# SchematicJSON.net
KiCad netlist of a schematic drawn in EasyEDA
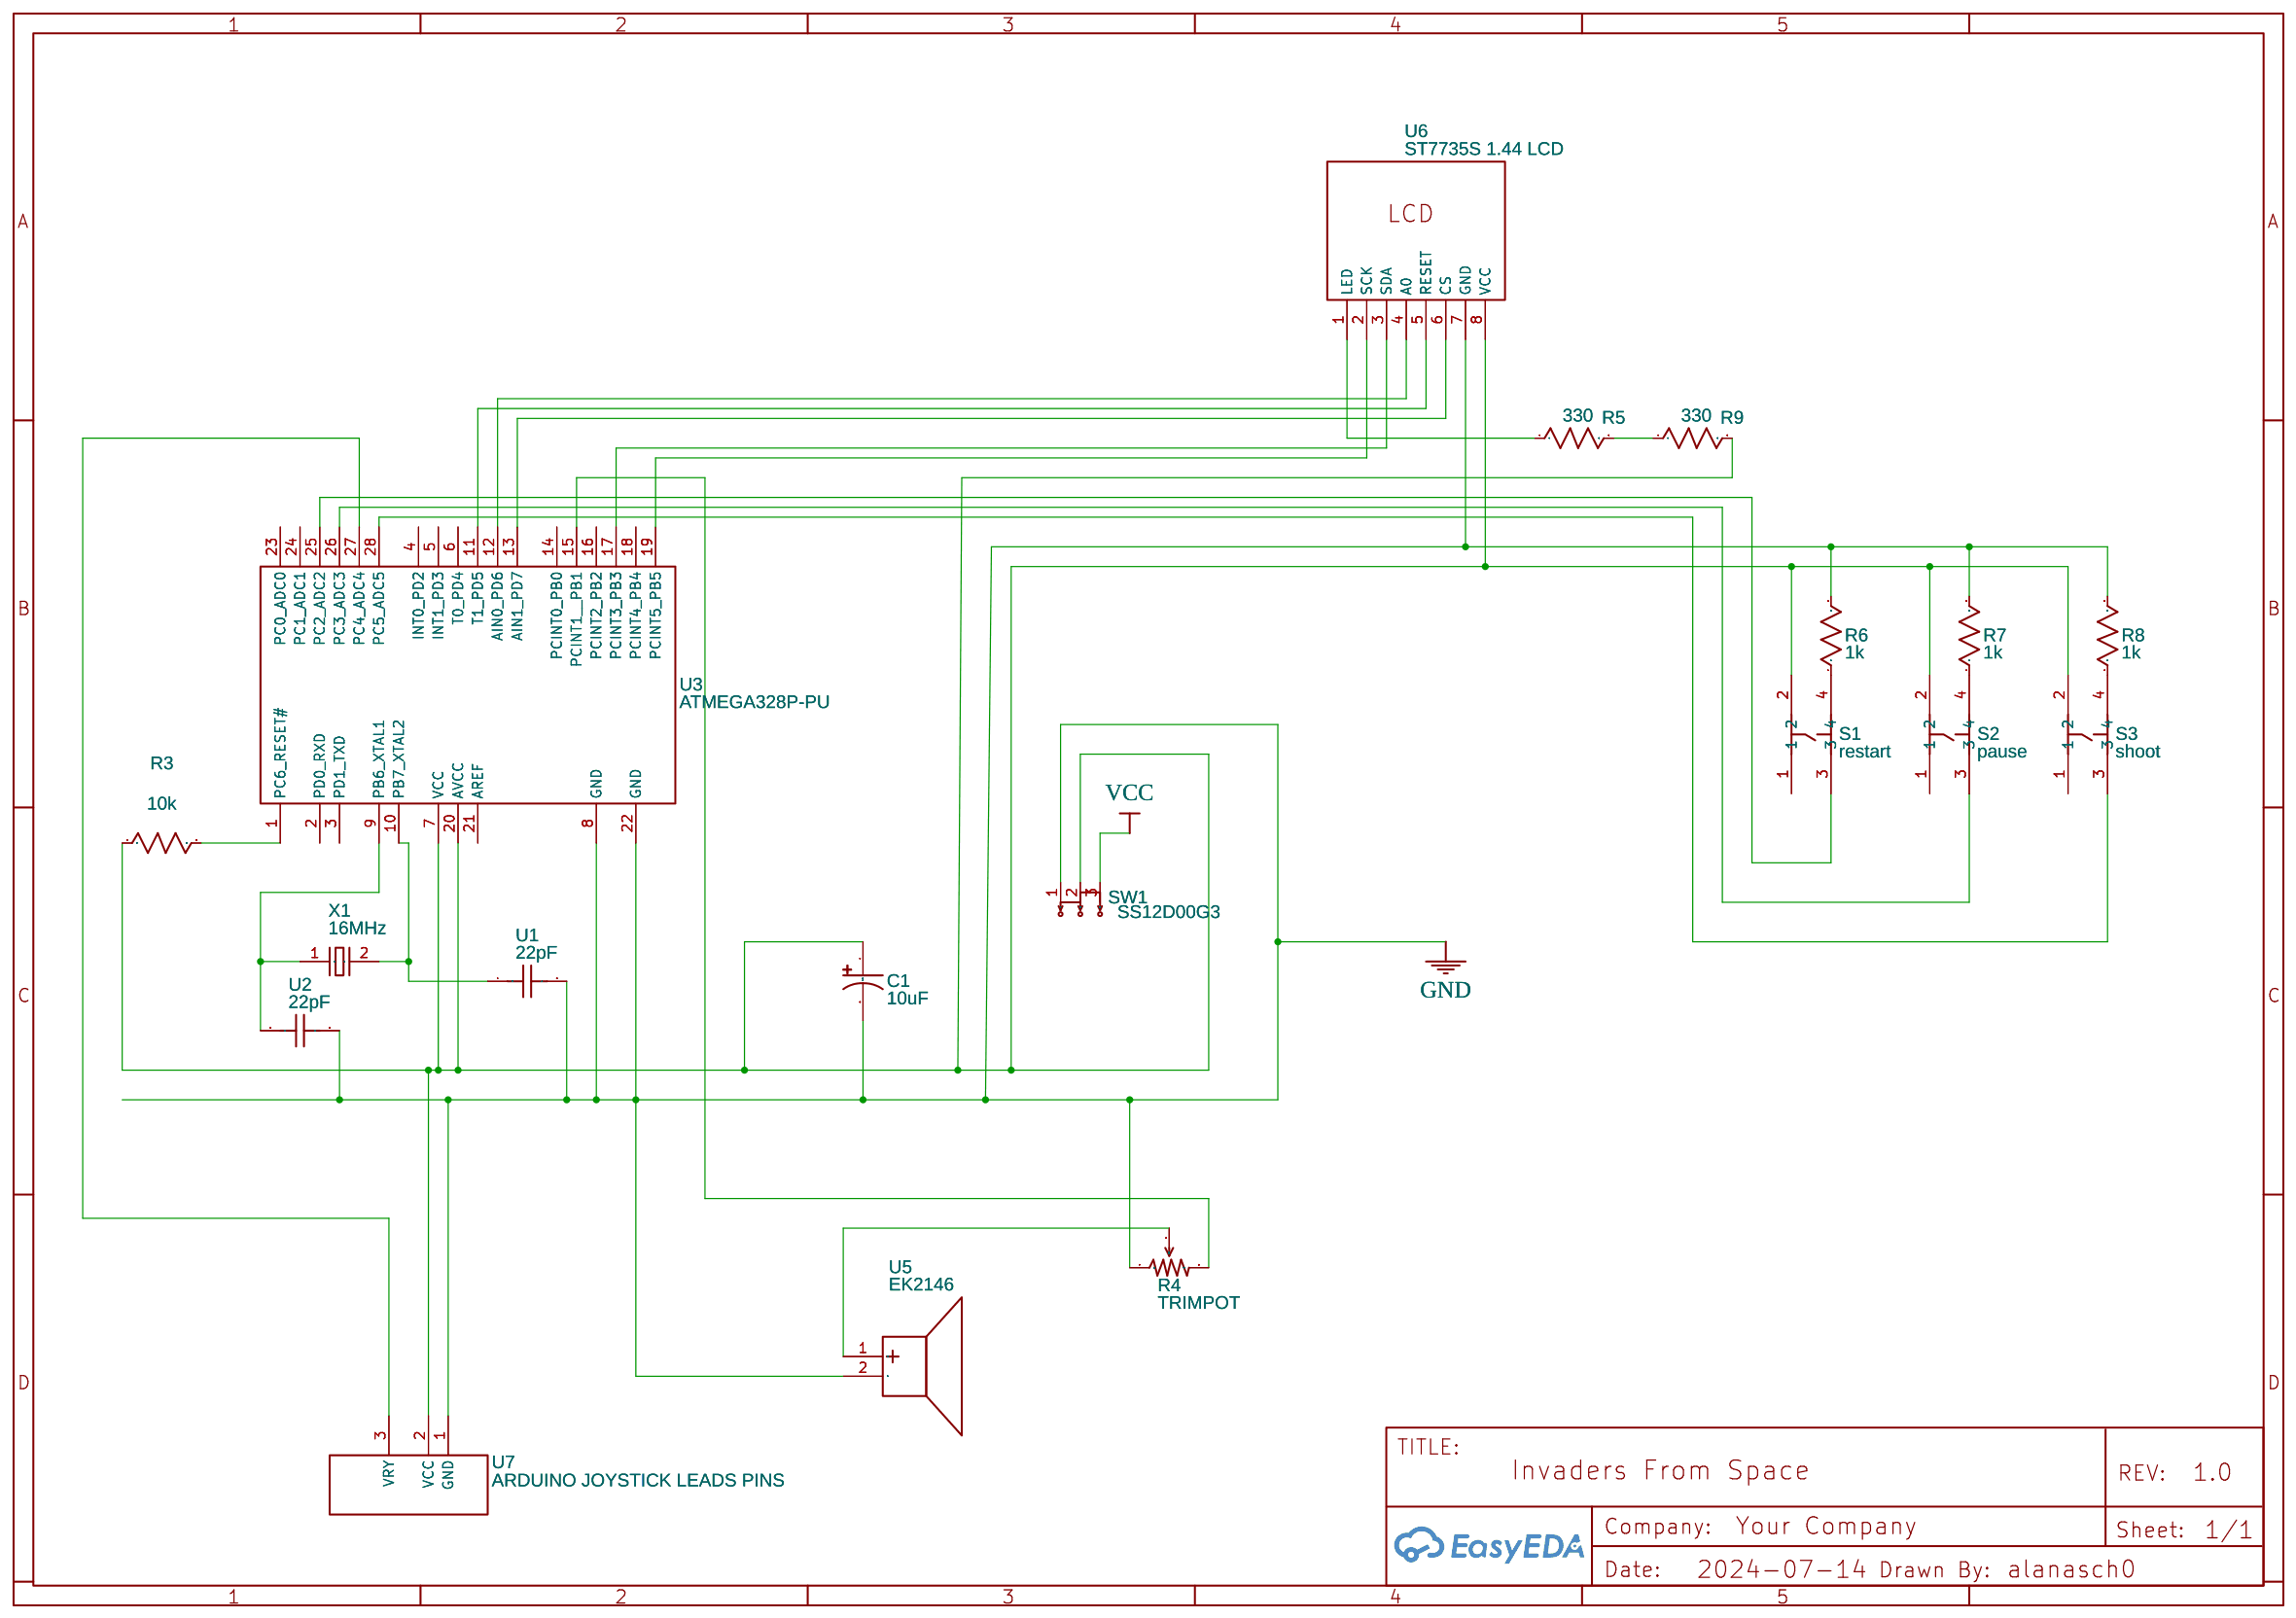
[diagram p0: schematic sheet]

(export (version "E")
  (design (tool "Eeschema 10.0.6"))
  (components
    (comp (ref "C1")
      (value "10uF")
      (fields
        (field (name "Manufacturer Part") "NFA 400V10 M 10*20")
        (field (name "Manufacturer") "SAMYOUNG(韩国三莹)")
      )
      (libsource (lib "") (part "NFA-400VB10-M-10*20"))
    )
    (comp (ref "R3") (value "10k") (libsource (lib "") (part "R_0603_US")))
    (comp (ref "R4") (value "TRIMPOT") (libsource (lib "") (part "TRIMPOT")))
    (comp (ref "R5") (value "330") (libsource (lib "") (part "R_0603_US")))
    (comp (ref "R6") (value "1k") (libsource (lib "") (part "R_0603_US_1")))
    (comp (ref "R7") (value "1k") (libsource (lib "") (part "R_0603_US_1")))
    (comp (ref "R8") (value "1k") (libsource (lib "") (part "R_0603_US_1")))
    (comp (ref "R9") (value "330") (libsource (lib "") (part "R_0603_US")))
    (comp (ref "S1")
      (value "restart")
      (fields (field (name "Manufacturer Part") "3101") (field (name "Manufacturer") "Adafruit"))
      (libsource (lib "") (part "Soft Tactile Button 8x8 (Adafruit 3101)"))
    )
    (comp (ref "S2")
      (value "pause")
      (fields (field (name "Manufacturer Part") "3101") (field (name "Manufacturer") "Adafruit"))
      (libsource (lib "") (part "Soft Tactile Button 8x8 (Adafruit 3101)"))
    )
    (comp (ref "S3")
      (value "shoot")
      (fields (field (name "Manufacturer Part") "3101") (field (name "Manufacturer") "Adafruit"))
      (libsource (lib "") (part "Soft Tactile Button 8x8 (Adafruit 3101)"))
    )
    (comp (ref "SW1") (value "SS12D00G3") (libsource (lib "") (part "SS12D00G3")))
    (comp (ref "U1")
      (value "22pF")
      (fields (field (name "Manufacturer Part") "K220J15C0GF53L2") (field (name "Manufacturer") "VISHAY(威世)"))
      (libsource (lib "") (part "K220J15C0GF53L2"))
    )
    (comp (ref "U2")
      (value "22pF")
      (fields (field (name "Manufacturer Part") "K220J15C0GF53L2") (field (name "Manufacturer") "VISHAY(威世)"))
      (libsource (lib "") (part "K220J15C0GF53L2"))
    )
    (comp (ref "U3")
      (value "ATMEGA328P-PU")
      (fields (field (name "Manufacturer") "MICROCHIP(美国微芯)"))
      (libsource (lib "") (part "ATMEGA328P-PU"))
    )
    (comp (ref "U5")
      (value "EK2146")
      (fields (field (name "Manufacturer") "Gikfun"))
      (libsource (lib "") (part "EK2146"))
    )
    (comp (ref "U6") (value "ST7735S 1.44 LCD") (libsource (lib "") (part "ST7735S 1.44 LCD")))
    (comp (ref "U7")
      (value "ARDUINO JOYSTICK LEADS PINS")
      (libsource (lib "") (part "ARDUINO JOYSTICK LEADS PINS"))
    )
    (comp (ref "X1")
      (value "16MHz")
      (fields
        (field (name "Manufacturer Part") "AS-16.000-18")
        (field (name "Manufacturer") "RALTRON(美国纬创电子)")
      )
      (libsource (lib "") (part "AS-16.000-18"))
    )
  )
  (nets
    (net (code "1") (name "GND") (class "Default")
      (node (ref "C1") (pin "2") (pinfunction "2_2") (pintype "unspecified"))
      (node (ref "R4") (pin "1") (pinfunction "CCW_1") (pintype "unspecified"))
      (node (ref "R6") (pin "2") (pinfunction "2_2") (pintype "unspecified"))
      (node (ref "R7") (pin "2") (pinfunction "2_2") (pintype "unspecified"))
      (node (ref "R8") (pin "2") (pinfunction "2_2") (pintype "unspecified"))
      (node (ref "SW1") (pin "1") (pinfunction "1_1") (pintype "unspecified"))
      (node (ref "U1") (pin "2") (pinfunction "2_2") (pintype "unspecified"))
      (node (ref "U2") (pin "2") (pinfunction "2_2") (pintype "unspecified"))
      (node (ref "U3") (pin "22") (pinfunction "GND_22") (pintype "passive"))
      (node (ref "U3") (pin "8") (pinfunction "GND_8") (pintype "passive"))
      (node (ref "U5") (pin "2") (pinfunction "2_2") (pintype "unspecified"))
      (node (ref "U6") (pin "7") (pinfunction "GND_7") (pintype "unspecified"))
      (node (ref "U7") (pin "1") (pinfunction "GND_1") (pintype "unspecified"))
    )
    (net (code "2") (name "Net-(R4-CW)") (class "Default")
      (node (ref "R4") (pin "3") (pinfunction "CW_3") (pintype "unspecified"))
      (node (ref "U3") (pin "15") (pinfunction "PCINT1__PB1_15") (pintype "bidirectional"))
    )
    (net (code "3") (name "Net-(R4-WIPER)") (class "Default")
      (node (ref "R4") (pin "2") (pinfunction "WIPER_2") (pintype "unspecified"))
      (node (ref "U5") (pin "1") (pinfunction "1_1") (pintype "unspecified"))
    )
    (net (code "4") (name "Net-(R5-Pad2)") (class "Default")
      (node (ref "R5") (pin "2") (pinfunction "2_2") (pintype "unspecified"))
      (node (ref "R9") (pin "1") (pinfunction "1_1") (pintype "unspecified"))
    )
    (net (code "5") (name "Net-(R6-Pad1)") (class "Default")
      (node (ref "R6") (pin "1") (pinfunction "1_1") (pintype "unspecified"))
      (node (ref "S1") (pin "4") (pinfunction "4_4") (pintype "unspecified"))
    )
    (net (code "6") (name "Net-(R7-Pad1)") (class "Default")
      (node (ref "R7") (pin "1") (pinfunction "1_1") (pintype "unspecified"))
      (node (ref "S2") (pin "4") (pinfunction "4_4") (pintype "unspecified"))
    )
    (net (code "7") (name "Net-(R8-Pad1)") (class "Default")
      (node (ref "R8") (pin "1") (pinfunction "1_1") (pintype "unspecified"))
      (node (ref "S3") (pin "4") (pinfunction "4_4") (pintype "unspecified"))
    )
    (net (code "8") (name "Net-(U3-AIN0_PD6)") (class "Default")
      (node (ref "U3") (pin "12") (pinfunction "AIN0_PD6_12") (pintype "bidirectional"))
      (node (ref "U6") (pin "4") (pinfunction "A0_4") (pintype "unspecified"))
    )
    (net (code "9") (name "Net-(U3-AIN1_PD7)") (class "Default")
      (node (ref "U3") (pin "13") (pinfunction "AIN1_PD7_13") (pintype "bidirectional"))
      (node (ref "U6") (pin "6") (pinfunction "CS_6") (pintype "unspecified"))
    )
    (net (code "10") (name "Net-(U3-AVCC)") (class "Default")
      (node (ref "C1") (pin "1") (pinfunction "1_1") (pintype "unspecified"))
      (node (ref "R3") (pin "1") (pinfunction "1_1") (pintype "unspecified"))
      (node (ref "R9") (pin "2") (pinfunction "2_2") (pintype "unspecified"))
      (node (ref "S1") (pin "2") (pinfunction "2_2") (pintype "unspecified"))
      (node (ref "S2") (pin "2") (pinfunction "2_2") (pintype "unspecified"))
      (node (ref "S3") (pin "2") (pinfunction "2_2") (pintype "unspecified"))
      (node (ref "SW1") (pin "2") (pinfunction "2_2") (pintype "unspecified"))
      (node (ref "U3") (pin "20") (pinfunction "AVCC_20") (pintype "passive"))
      (node (ref "U3") (pin "7") (pinfunction "VCC_7") (pintype "passive"))
      (node (ref "U6") (pin "8") (pinfunction "VCC_8") (pintype "unspecified"))
      (node (ref "U7") (pin "2") (pinfunction "VCC_2") (pintype "unspecified"))
    )
    (net (code "11") (name "Net-(U3-PB6_XTAL1)") (class "Default")
      (node (ref "U2") (pin "1") (pinfunction "1_1") (pintype "unspecified"))
      (node (ref "U3") (pin "9") (pinfunction "PB6_XTAL1_9") (pintype "bidirectional"))
      (node (ref "X1") (pin "1") (pinfunction "1_1") (pintype "input"))
    )
    (net (code "12") (name "Net-(U3-PB7_XTAL2)") (class "Default")
      (node (ref "U1") (pin "1") (pinfunction "1_1") (pintype "unspecified"))
      (node (ref "U3") (pin "10") (pinfunction "PB7_XTAL2_10") (pintype "bidirectional"))
      (node (ref "X1") (pin "2") (pinfunction "2_2") (pintype "input"))
    )
    (net (code "13") (name "Net-(U3-PC2_ADC2)") (class "Default")
      (node (ref "S1") (pin "3") (pinfunction "3_3") (pintype "unspecified"))
      (node (ref "U3") (pin "25") (pinfunction "PC2_ADC2_25") (pintype "bidirectional"))
    )
    (net (code "14") (name "Net-(U3-PC3_ADC3)") (class "Default")
      (node (ref "S2") (pin "3") (pinfunction "3_3") (pintype "unspecified"))
      (node (ref "U3") (pin "26") (pinfunction "PC3_ADC3_26") (pintype "bidirectional"))
    )
    (net (code "15") (name "Net-(U3-PC4_ADC4)") (class "Default")
      (node (ref "U3") (pin "27") (pinfunction "PC4_ADC4_27") (pintype "bidirectional"))
      (node (ref "U7") (pin "3") (pinfunction "VRY_3") (pintype "unspecified"))
    )
    (net (code "16") (name "Net-(U3-PC5_ADC5)") (class "Default")
      (node (ref "S3") (pin "3") (pinfunction "3_3") (pintype "unspecified"))
      (node (ref "U3") (pin "28") (pinfunction "PC5_ADC5_28") (pintype "bidirectional"))
    )
    (net (code "17") (name "Net-(U3-PC6_RESET#)") (class "Default")
      (node (ref "R3") (pin "2") (pinfunction "2_2") (pintype "unspecified"))
      (node (ref "U3") (pin "1") (pinfunction "PC6_RESET#_1") (pintype "bidirectional"))
    )
    (net (code "18") (name "Net-(U3-PCINT3_PB3)") (class "Default")
      (node (ref "U3") (pin "17") (pinfunction "PCINT3_PB3_17") (pintype "bidirectional"))
      (node (ref "U6") (pin "3") (pinfunction "SDA_3") (pintype "unspecified"))
    )
    (net (code "19") (name "Net-(U3-PCINT5_PB5)") (class "Default")
      (node (ref "U3") (pin "19") (pinfunction "PCINT5_PB5_19") (pintype "bidirectional"))
      (node (ref "U6") (pin "2") (pinfunction "SCK_2") (pintype "unspecified"))
    )
    (net (code "20") (name "Net-(U3-T1_PD5)") (class "Default")
      (node (ref "U3") (pin "11") (pinfunction "T1_PD5_11") (pintype "bidirectional"))
      (node (ref "U6") (pin "5") (pinfunction "RESET_5") (pintype "unspecified"))
    )
    (net (code "21") (name "Net-(U6-LED)") (class "Default")
      (node (ref "R5") (pin "1") (pinfunction "1_1") (pintype "unspecified"))
      (node (ref "U6") (pin "1") (pinfunction "LED_1") (pintype "unspecified"))
    )
    (net (code "22") (name "VCC") (class "Default")
      (node (ref "SW1") (pin "3") (pinfunction "3_3") (pintype "unspecified"))
    )
    (net (code "23") (name "unconnected-(S1-Pad1)") (class "Default")
      (node (ref "S1") (pin "1") (pinfunction "1_1") (pintype "unspecified"))
    )
    (net (code "24") (name "unconnected-(S2-Pad1)") (class "Default")
      (node (ref "S2") (pin "1") (pinfunction "1_1") (pintype "unspecified"))
    )
    (net (code "25") (name "unconnected-(S3-Pad1)") (class "Default")
      (node (ref "S3") (pin "1") (pinfunction "1_1") (pintype "unspecified"))
    )
    (net (code "26") (name "unconnected-(U3-AREF-Pad21)") (class "Default")
      (node (ref "U3") (pin "21") (pinfunction "AREF_21") (pintype "passive"))
    )
    (net (code "27") (name "unconnected-(U3-INT0_PD2-Pad4)") (class "Default")
      (node (ref "U3") (pin "4") (pinfunction "INT0_PD2_4") (pintype "bidirectional"))
    )
    (net (code "28") (name "unconnected-(U3-INT1_PD3-Pad5)") (class "Default")
      (node (ref "U3") (pin "5") (pinfunction "INT1_PD3_5") (pintype "bidirectional"))
    )
    (net (code "29") (name "unconnected-(U3-PC0_ADC0-Pad23)") (class "Default")
      (node (ref "U3") (pin "23") (pinfunction "PC0_ADC0_23") (pintype "bidirectional"))
    )
    (net (code "30") (name "unconnected-(U3-PC1_ADC1-Pad24)") (class "Default")
      (node (ref "U3") (pin "24") (pinfunction "PC1_ADC1_24") (pintype "bidirectional"))
    )
    (net (code "31") (name "unconnected-(U3-PCINT0_PB0-Pad14)") (class "Default")
      (node (ref "U3") (pin "14") (pinfunction "PCINT0_PB0_14") (pintype "bidirectional"))
    )
    (net (code "32") (name "unconnected-(U3-PCINT2_PB2-Pad16)") (class "Default")
      (node (ref "U3") (pin "16") (pinfunction "PCINT2_PB2_16") (pintype "bidirectional"))
    )
    (net (code "33") (name "unconnected-(U3-PCINT4_PB4-Pad18)") (class "Default")
      (node (ref "U3") (pin "18") (pinfunction "PCINT4_PB4_18") (pintype "bidirectional"))
    )
    (net (code "34") (name "unconnected-(U3-PD0_RXD-Pad2)") (class "Default")
      (node (ref "U3") (pin "2") (pinfunction "PD0_RXD_2") (pintype "bidirectional"))
    )
    (net (code "35") (name "unconnected-(U3-PD1_TXD-Pad3)") (class "Default")
      (node (ref "U3") (pin "3") (pinfunction "PD1_TXD_3") (pintype "bidirectional"))
    )
    (net (code "36") (name "unconnected-(U3-T0_PD4-Pad6)") (class "Default")
      (node (ref "U3") (pin "6") (pinfunction "T0_PD4_6") (pintype "bidirectional"))
    )
  )
)
